# 4_CONN.net
KiCad netlist of a schematic drawn in Altium Designer
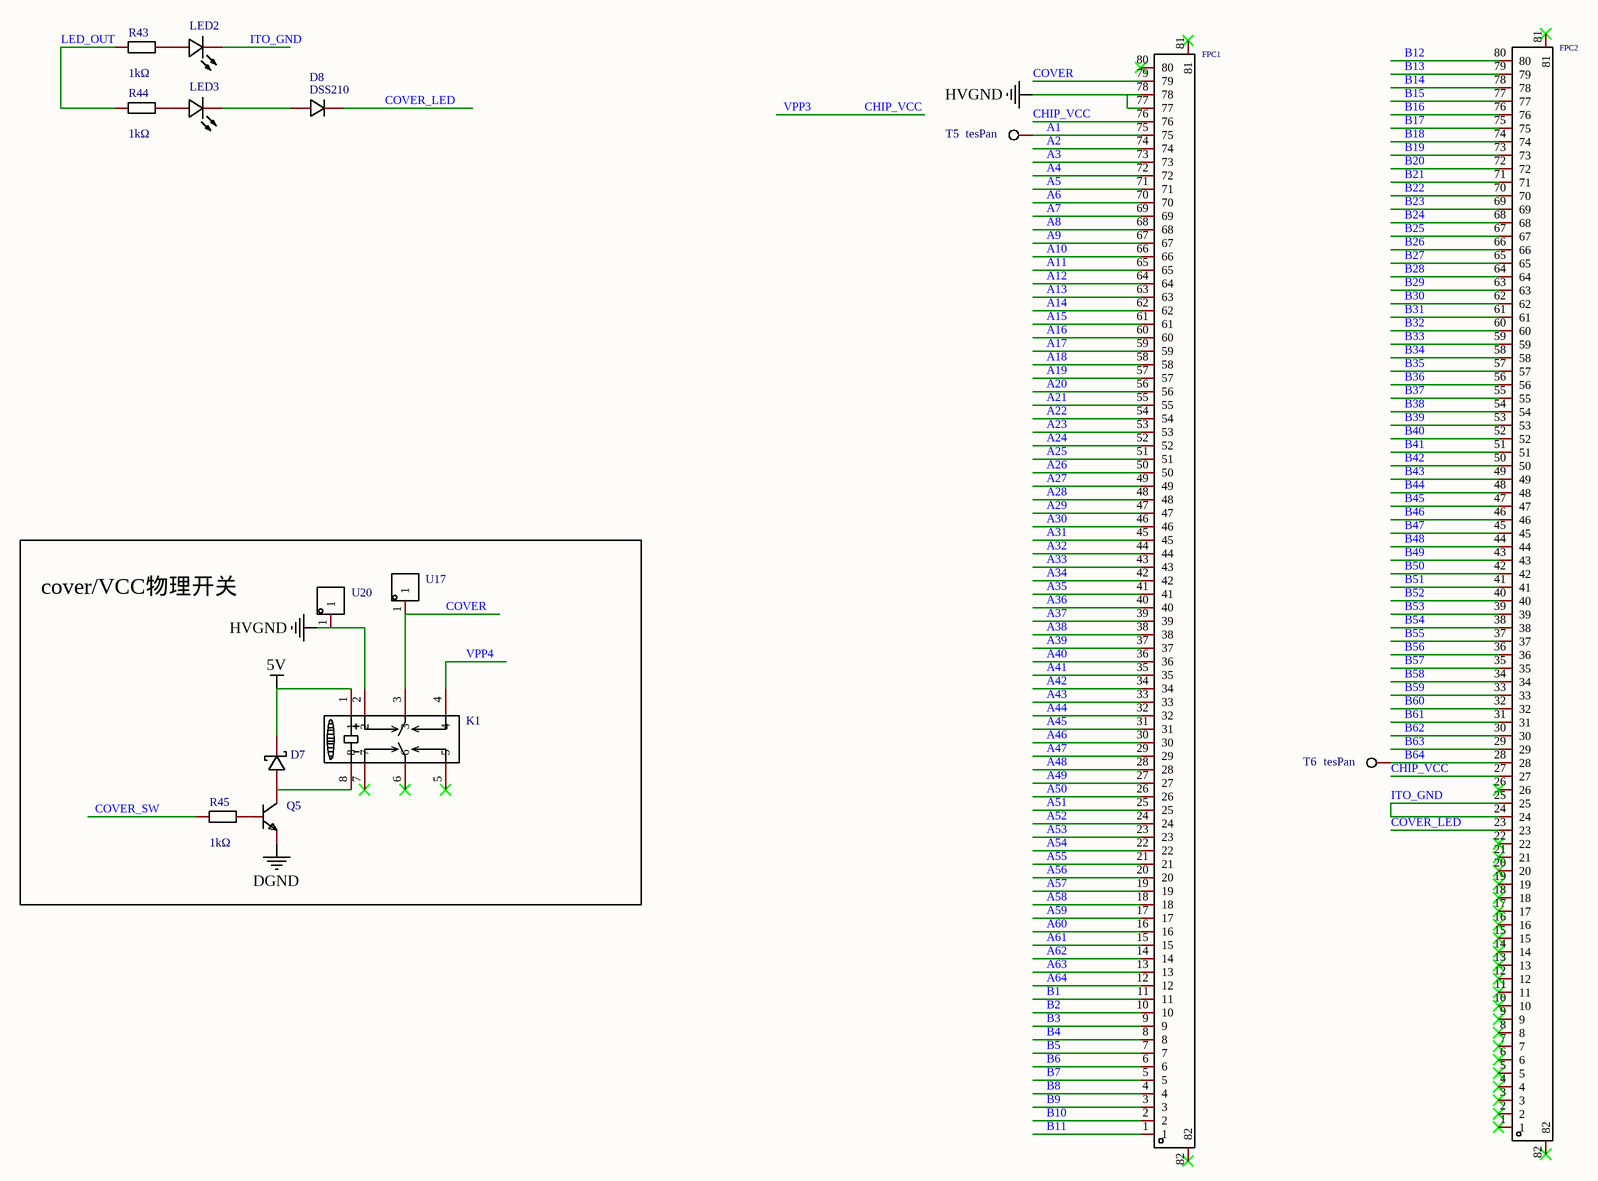
[diagram p0: 4_CONN.schdoc]

(export (version "E")
  (design (tool "Eeschema 10.0.6"))
  (components
    (comp (ref "D7")
      (value "B5819W SL")
      (description "直流反向耐压(Vr):40V;平均整流电流(Io):1A;正向压降(Vf):600mV@1A;")
      (fields (field (name "MANUFACTURER") "CJ(江苏长电/长晶)"))
      (libsource (lib "altium-import") (part "root_3_B5819W SL_"))
    )
    (comp (ref "D8")
      (value "DSS210")
      (fields (field (name "NAME") "DSS210") (field (name "MANUFACTURER") "Bourne Semicon (Shenzhen)"))
      (libsource (lib "altium-import") (part "root_0_DSS210_SOD-123_L2.8-W1.8-LS3.7-FD_"))
    )
    (comp (ref "FPC1")
      (value "FH28H-80S-0.5SH(05)")
      (description "间距:0.5mm;触点数量:80;锁定特性:翻盖式;安装类型:卧贴;触点类型:下接;")
      (fields (field (name "MANUFACTURER") "HRS(广濑)"))
      (libsource (lib "altium-import") (part "root_2_mirrored_FH28H-80S-0.5SH(05)_"))
    )
    (comp (ref "FPC2")
      (value "FH28H-80S-0.5SH(05)")
      (description "间距:0.5mm;触点数量:80;锁定特性:翻盖式;安装类型:卧贴;触点类型:下接;")
      (fields (field (name "MANUFACTURER") "HRS(广濑)"))
      (libsource (lib "altium-import") (part "root_2_mirrored_FH28H-80S-0.5SH(05)_"))
    )
    (comp (ref "K1")
      (value "G6K-2F-Y-TR DC5")
      (description "线圈电压:-;触点形式:-;最大切换电压:-;最大切换电流:-;线圈类型:-;触点材料:-;")
      (fields (field (name "MANUFACTURER") "OMRON(欧姆龙)"))
      (libsource (lib "altium-import") (part "root_2_mirrored_G6K-2F-Y-TR DC5_"))
    )
    (comp (ref "LED2")
      (value "LED0402-YELLOW")
      (libsource (lib "altium-import") (part "root_2_LED0402-YELLOW_"))
    )
    (comp (ref "LED3")
      (value "LED0402-YELLOW")
      (libsource (lib "altium-import") (part "root_2_LED0402-YELLOW_"))
    )
    (comp (ref "Q5")
      (value "S8050 J3Y_C2146")
      (fields (field (name "MANUFACTURER") "CJ(江苏长电/长晶)") (field (name "MANUFACTURER PART") "S8050 J3Y"))
      (libsource (lib "altium-import") (part "root_0_S8050 J3Y_C2146_"))
    )
    (comp (ref "R43")
      (value "1kΩ")
      (description "电阻类型:厚膜电阻;阻值:1kΩ;精度:±1%;功率:62.5mW;")
      (fields
        (field (name "MANUFACTURER") "UNI-ROYAL(厚声)")
        (field (name "MANUFACTURER PART") "0402WGF1001TCE")
      )
      (libsource (lib "altium-import") (part "root_0_0402WGF1001TCE_"))
    )
    (comp (ref "R44")
      (value "1kΩ")
      (description "电阻类型:厚膜电阻;阻值:1kΩ;精度:±1%;功率:62.5mW;")
      (fields
        (field (name "MANUFACTURER") "UNI-ROYAL(厚声)")
        (field (name "MANUFACTURER PART") "0402WGF1001TCE")
      )
      (libsource (lib "altium-import") (part "root_0_0402WGF1001TCE_"))
    )
    (comp (ref "R45")
      (value "1kΩ")
      (description "电阻类型:厚膜电阻;阻值:1kΩ;精度:±1%;功率:62.5mW;")
      (fields
        (field (name "MANUFACTURER") "UNI-ROYAL(厚声)")
        (field (name "MANUFACTURER PART") "0402WGF1001TCE")
      )
      (libsource (lib "altium-import") (part "root_0_0402WGF1001TCE_"))
    )
    (comp (ref "T5")
      (value "tesPan")
      (fields (field (name "NAME") "tesPan"))
      (libsource (lib "altium-import") (part "root_1_tesPan_"))
    )
    (comp (ref "T6")
      (value "tesPan")
      (fields (field (name "NAME") "tesPan"))
      (libsource (lib "altium-import") (part "root_1_tesPan_"))
    )
    (comp (ref "U17")
      (value "5003")
      (description "类型:测试环;全长/全高:7.62mm;工作高度:-;接触电阻:-;弹性寿命:-;额定电流:-;额定电压:-;触头材质:磷青铜;触头镀层:-;工作温度范围:-;")
      (fields (field (name "MANUFACTURER") "Keystone"))
      (libsource (lib "altium-import") (part "root_1_5003_"))
    )
    (comp (ref "U20")
      (value "5003")
      (description "类型:测试环;全长/全高:7.62mm;工作高度:-;接触电阻:-;弹性寿命:-;额定电流:-;额定电压:-;触头材质:磷青铜;触头镀层:-;工作温度范围:-;")
      (fields (field (name "MANUFACTURER") "Keystone"))
      (libsource (lib "altium-import") (part "root_1_5003_"))
    )
  )
  (nets
    (net (code "1") (name "/A1") (class "Default")
      (node (ref "FPC1") (pin "75") (pinfunction "75_75") (pintype "passive"))
      (node (ref "T5") (pin "1") (pinfunction "1_1") (pintype "passive"))
    )
    (net (code "2") (name "/A2") (class "Default")
      (node (ref "FPC1") (pin "74") (pinfunction "74_74") (pintype "passive"))
    )
    (net (code "3") (name "/A3") (class "Default")
      (node (ref "FPC1") (pin "73") (pinfunction "73_73") (pintype "passive"))
    )
    (net (code "4") (name "/A4") (class "Default")
      (node (ref "FPC1") (pin "72") (pinfunction "72_72") (pintype "passive"))
    )
    (net (code "5") (name "/A5") (class "Default")
      (node (ref "FPC1") (pin "71") (pinfunction "71_71") (pintype "passive"))
    )
    (net (code "6") (name "/A6") (class "Default")
      (node (ref "FPC1") (pin "70") (pinfunction "70_70") (pintype "passive"))
    )
    (net (code "7") (name "/A7") (class "Default")
      (node (ref "FPC1") (pin "69") (pinfunction "69_69") (pintype "passive"))
    )
    (net (code "8") (name "/A8") (class "Default")
      (node (ref "FPC1") (pin "68") (pinfunction "68_68") (pintype "passive"))
    )
    (net (code "9") (name "/A9") (class "Default")
      (node (ref "FPC1") (pin "67") (pinfunction "67_67") (pintype "passive"))
    )
    (net (code "10") (name "/A10") (class "Default")
      (node (ref "FPC1") (pin "66") (pinfunction "66_66") (pintype "passive"))
    )
    (net (code "11") (name "/A11") (class "Default")
      (node (ref "FPC1") (pin "65") (pinfunction "65_65") (pintype "passive"))
    )
    (net (code "12") (name "/A12") (class "Default")
      (node (ref "FPC1") (pin "64") (pinfunction "64_64") (pintype "passive"))
    )
    (net (code "13") (name "/A13") (class "Default")
      (node (ref "FPC1") (pin "63") (pinfunction "63_63") (pintype "passive"))
    )
    (net (code "14") (name "/A14") (class "Default")
      (node (ref "FPC1") (pin "62") (pinfunction "62_62") (pintype "passive"))
    )
    (net (code "15") (name "/A15") (class "Default")
      (node (ref "FPC1") (pin "61") (pinfunction "61_61") (pintype "passive"))
    )
    (net (code "16") (name "/A16") (class "Default")
      (node (ref "FPC1") (pin "60") (pinfunction "60_60") (pintype "passive"))
    )
    (net (code "17") (name "/A17") (class "Default")
      (node (ref "FPC1") (pin "59") (pinfunction "59_59") (pintype "passive"))
    )
    (net (code "18") (name "/A18") (class "Default")
      (node (ref "FPC1") (pin "58") (pinfunction "58_58") (pintype "passive"))
    )
    (net (code "19") (name "/A19") (class "Default")
      (node (ref "FPC1") (pin "57") (pinfunction "57_57") (pintype "passive"))
    )
    (net (code "20") (name "/A20") (class "Default")
      (node (ref "FPC1") (pin "56") (pinfunction "56_56") (pintype "passive"))
    )
    (net (code "21") (name "/A21") (class "Default")
      (node (ref "FPC1") (pin "55") (pinfunction "55_55") (pintype "passive"))
    )
    (net (code "22") (name "/A22") (class "Default")
      (node (ref "FPC1") (pin "54") (pinfunction "54_54") (pintype "passive"))
    )
    (net (code "23") (name "/A23") (class "Default")
      (node (ref "FPC1") (pin "53") (pinfunction "53_53") (pintype "passive"))
    )
    (net (code "24") (name "/A24") (class "Default")
      (node (ref "FPC1") (pin "52") (pinfunction "52_52") (pintype "passive"))
    )
    (net (code "25") (name "/A25") (class "Default")
      (node (ref "FPC1") (pin "51") (pinfunction "51_51") (pintype "passive"))
    )
    (net (code "26") (name "/A26") (class "Default")
      (node (ref "FPC1") (pin "50") (pinfunction "50_50") (pintype "passive"))
    )
    (net (code "27") (name "/A27") (class "Default")
      (node (ref "FPC1") (pin "49") (pinfunction "49_49") (pintype "passive"))
    )
    (net (code "28") (name "/A28") (class "Default")
      (node (ref "FPC1") (pin "48") (pinfunction "48_48") (pintype "passive"))
    )
    (net (code "29") (name "/A29") (class "Default")
      (node (ref "FPC1") (pin "47") (pinfunction "47_47") (pintype "passive"))
    )
    (net (code "30") (name "/A30") (class "Default")
      (node (ref "FPC1") (pin "46") (pinfunction "46_46") (pintype "passive"))
    )
    (net (code "31") (name "/A31") (class "Default")
      (node (ref "FPC1") (pin "45") (pinfunction "45_45") (pintype "passive"))
    )
    (net (code "32") (name "/A32") (class "Default")
      (node (ref "FPC1") (pin "44") (pinfunction "44_44") (pintype "passive"))
    )
    (net (code "33") (name "/A33") (class "Default")
      (node (ref "FPC1") (pin "43") (pinfunction "43_43") (pintype "passive"))
    )
    (net (code "34") (name "/A34") (class "Default")
      (node (ref "FPC1") (pin "42") (pinfunction "42_42") (pintype "passive"))
    )
    (net (code "35") (name "/A35") (class "Default")
      (node (ref "FPC1") (pin "41") (pinfunction "41_41") (pintype "passive"))
    )
    (net (code "36") (name "/A36") (class "Default")
      (node (ref "FPC1") (pin "40") (pinfunction "40_40") (pintype "passive"))
    )
    (net (code "37") (name "/A37") (class "Default")
      (node (ref "FPC1") (pin "39") (pinfunction "39_39") (pintype "passive"))
    )
    (net (code "38") (name "/A38") (class "Default")
      (node (ref "FPC1") (pin "38") (pinfunction "38_38") (pintype "passive"))
    )
    (net (code "39") (name "/A39") (class "Default")
      (node (ref "FPC1") (pin "37") (pinfunction "37_37") (pintype "passive"))
    )
    (net (code "40") (name "/A40") (class "Default")
      (node (ref "FPC1") (pin "36") (pinfunction "36_36") (pintype "passive"))
    )
    (net (code "41") (name "/A41") (class "Default")
      (node (ref "FPC1") (pin "35") (pinfunction "35_35") (pintype "passive"))
    )
    (net (code "42") (name "/A42") (class "Default")
      (node (ref "FPC1") (pin "34") (pinfunction "34_34") (pintype "passive"))
    )
    (net (code "43") (name "/A43") (class "Default")
      (node (ref "FPC1") (pin "33") (pinfunction "33_33") (pintype "passive"))
    )
    (net (code "44") (name "/A44") (class "Default")
      (node (ref "FPC1") (pin "32") (pinfunction "32_32") (pintype "passive"))
    )
    (net (code "45") (name "/A45") (class "Default")
      (node (ref "FPC1") (pin "31") (pinfunction "31_31") (pintype "passive"))
    )
    (net (code "46") (name "/A46") (class "Default")
      (node (ref "FPC1") (pin "30") (pinfunction "30_30") (pintype "passive"))
    )
    (net (code "47") (name "/A47") (class "Default")
      (node (ref "FPC1") (pin "29") (pinfunction "29_29") (pintype "passive"))
    )
    (net (code "48") (name "/A48") (class "Default")
      (node (ref "FPC1") (pin "28") (pinfunction "28_28") (pintype "passive"))
    )
    (net (code "49") (name "/A49") (class "Default")
      (node (ref "FPC1") (pin "27") (pinfunction "27_27") (pintype "passive"))
    )
    (net (code "50") (name "/A50") (class "Default")
      (node (ref "FPC1") (pin "26") (pinfunction "26_26") (pintype "passive"))
    )
    (net (code "51") (name "/A51") (class "Default")
      (node (ref "FPC1") (pin "25") (pinfunction "25_25") (pintype "passive"))
    )
    (net (code "52") (name "/A52") (class "Default")
      (node (ref "FPC1") (pin "24") (pinfunction "24_24") (pintype "passive"))
    )
    (net (code "53") (name "/A53") (class "Default")
      (node (ref "FPC1") (pin "23") (pinfunction "23_23") (pintype "passive"))
    )
    (net (code "54") (name "/A54") (class "Default")
      (node (ref "FPC1") (pin "22") (pinfunction "22_22") (pintype "passive"))
    )
    (net (code "55") (name "/A55") (class "Default")
      (node (ref "FPC1") (pin "21") (pinfunction "21_21") (pintype "passive"))
    )
    (net (code "56") (name "/A56") (class "Default")
      (node (ref "FPC1") (pin "20") (pinfunction "20_20") (pintype "passive"))
    )
    (net (code "57") (name "/A57") (class "Default")
      (node (ref "FPC1") (pin "19") (pinfunction "19_19") (pintype "passive"))
    )
    (net (code "58") (name "/A58") (class "Default")
      (node (ref "FPC1") (pin "18") (pinfunction "18_18") (pintype "passive"))
    )
    (net (code "59") (name "/A59") (class "Default")
      (node (ref "FPC1") (pin "17") (pinfunction "17_17") (pintype "passive"))
    )
    (net (code "60") (name "/A60") (class "Default")
      (node (ref "FPC1") (pin "16") (pinfunction "16_16") (pintype "passive"))
    )
    (net (code "61") (name "/A61") (class "Default")
      (node (ref "FPC1") (pin "15") (pinfunction "15_15") (pintype "passive"))
    )
    (net (code "62") (name "/A62") (class "Default")
      (node (ref "FPC1") (pin "14") (pinfunction "14_14") (pintype "passive"))
    )
    (net (code "63") (name "/A63") (class "Default")
      (node (ref "FPC1") (pin "13") (pinfunction "13_13") (pintype "passive"))
    )
    (net (code "64") (name "/A64") (class "Default")
      (node (ref "FPC1") (pin "12") (pinfunction "12_12") (pintype "passive"))
    )
    (net (code "65") (name "/B1") (class "Default")
      (node (ref "FPC1") (pin "11") (pinfunction "11_11") (pintype "passive"))
    )
    (net (code "66") (name "/B2") (class "Default")
      (node (ref "FPC1") (pin "10") (pinfunction "10_10") (pintype "passive"))
    )
    (net (code "67") (name "/B3") (class "Default")
      (node (ref "FPC1") (pin "9") (pinfunction "9_9") (pintype "passive"))
    )
    (net (code "68") (name "/B4") (class "Default")
      (node (ref "FPC1") (pin "8") (pinfunction "8_8") (pintype "passive"))
    )
    (net (code "69") (name "/B5") (class "Default")
      (node (ref "FPC1") (pin "7") (pinfunction "7_7") (pintype "passive"))
    )
    (net (code "70") (name "/B6") (class "Default")
      (node (ref "FPC1") (pin "6") (pinfunction "6_6") (pintype "passive"))
    )
    (net (code "71") (name "/B7") (class "Default")
      (node (ref "FPC1") (pin "5") (pinfunction "5_5") (pintype "passive"))
    )
    (net (code "72") (name "/B8") (class "Default")
      (node (ref "FPC1") (pin "4") (pinfunction "4_4") (pintype "passive"))
    )
    (net (code "73") (name "/B9") (class "Default")
      (node (ref "FPC1") (pin "3") (pinfunction "3_3") (pintype "passive"))
    )
    (net (code "74") (name "/B10") (class "Default")
      (node (ref "FPC1") (pin "2") (pinfunction "2_2") (pintype "passive"))
    )
    (net (code "75") (name "/B11") (class "Default")
      (node (ref "FPC1") (pin "1") (pinfunction "1_1") (pintype "passive"))
    )
    (net (code "76") (name "/B12") (class "Default")
      (node (ref "FPC2") (pin "80") (pinfunction "80_80") (pintype "passive"))
    )
    (net (code "77") (name "/B13") (class "Default")
      (node (ref "FPC2") (pin "79") (pinfunction "79_79") (pintype "passive"))
    )
    (net (code "78") (name "/B14") (class "Default")
      (node (ref "FPC2") (pin "78") (pinfunction "78_78") (pintype "passive"))
    )
    (net (code "79") (name "/B15") (class "Default")
      (node (ref "FPC2") (pin "77") (pinfunction "77_77") (pintype "passive"))
    )
    (net (code "80") (name "/B16") (class "Default")
      (node (ref "FPC2") (pin "76") (pinfunction "76_76") (pintype "passive"))
    )
    (net (code "81") (name "/B17") (class "Default")
      (node (ref "FPC2") (pin "75") (pinfunction "75_75") (pintype "passive"))
    )
    (net (code "82") (name "/B18") (class "Default")
      (node (ref "FPC2") (pin "74") (pinfunction "74_74") (pintype "passive"))
    )
    (net (code "83") (name "/B19") (class "Default")
      (node (ref "FPC2") (pin "73") (pinfunction "73_73") (pintype "passive"))
    )
    (net (code "84") (name "/B20") (class "Default")
      (node (ref "FPC2") (pin "72") (pinfunction "72_72") (pintype "passive"))
    )
    (net (code "85") (name "/B21") (class "Default")
      (node (ref "FPC2") (pin "71") (pinfunction "71_71") (pintype "passive"))
    )
    (net (code "86") (name "/B22") (class "Default")
      (node (ref "FPC2") (pin "70") (pinfunction "70_70") (pintype "passive"))
    )
    (net (code "87") (name "/B23") (class "Default")
      (node (ref "FPC2") (pin "69") (pinfunction "69_69") (pintype "passive"))
    )
    (net (code "88") (name "/B24") (class "Default")
      (node (ref "FPC2") (pin "68") (pinfunction "68_68") (pintype "passive"))
    )
    (net (code "89") (name "/B25") (class "Default")
      (node (ref "FPC2") (pin "67") (pinfunction "67_67") (pintype "passive"))
    )
    (net (code "90") (name "/B26") (class "Default")
      (node (ref "FPC2") (pin "66") (pinfunction "66_66") (pintype "passive"))
    )
    (net (code "91") (name "/B27") (class "Default")
      (node (ref "FPC2") (pin "65") (pinfunction "65_65") (pintype "passive"))
    )
    (net (code "92") (name "/B28") (class "Default")
      (node (ref "FPC2") (pin "64") (pinfunction "64_64") (pintype "passive"))
    )
    (net (code "93") (name "/B29") (class "Default")
      (node (ref "FPC2") (pin "63") (pinfunction "63_63") (pintype "passive"))
    )
    (net (code "94") (name "/B30") (class "Default")
      (node (ref "FPC2") (pin "62") (pinfunction "62_62") (pintype "passive"))
    )
    (net (code "95") (name "/B31") (class "Default")
      (node (ref "FPC2") (pin "61") (pinfunction "61_61") (pintype "passive"))
    )
    (net (code "96") (name "/B32") (class "Default")
      (node (ref "FPC2") (pin "60") (pinfunction "60_60") (pintype "passive"))
    )
    (net (code "97") (name "/B33") (class "Default")
      (node (ref "FPC2") (pin "59") (pinfunction "59_59") (pintype "passive"))
    )
    (net (code "98") (name "/B34") (class "Default")
      (node (ref "FPC2") (pin "58") (pinfunction "58_58") (pintype "passive"))
    )
    (net (code "99") (name "/B35") (class "Default")
      (node (ref "FPC2") (pin "57") (pinfunction "57_57") (pintype "passive"))
    )
    (net (code "100") (name "/B36") (class "Default")
      (node (ref "FPC2") (pin "56") (pinfunction "56_56") (pintype "passive"))
    )
    (net (code "101") (name "/B37") (class "Default")
      (node (ref "FPC2") (pin "55") (pinfunction "55_55") (pintype "passive"))
    )
    (net (code "102") (name "/B38") (class "Default")
      (node (ref "FPC2") (pin "54") (pinfunction "54_54") (pintype "passive"))
    )
    (net (code "103") (name "/B39") (class "Default")
      (node (ref "FPC2") (pin "53") (pinfunction "53_53") (pintype "passive"))
    )
    (net (code "104") (name "/B40") (class "Default")
      (node (ref "FPC2") (pin "52") (pinfunction "52_52") (pintype "passive"))
    )
    (net (code "105") (name "/B41") (class "Default")
      (node (ref "FPC2") (pin "51") (pinfunction "51_51") (pintype "passive"))
    )
    (net (code "106") (name "/B42") (class "Default")
      (node (ref "FPC2") (pin "50") (pinfunction "50_50") (pintype "passive"))
    )
    (net (code "107") (name "/B43") (class "Default")
      (node (ref "FPC2") (pin "49") (pinfunction "49_49") (pintype "passive"))
    )
    (net (code "108") (name "/B44") (class "Default")
      (node (ref "FPC2") (pin "48") (pinfunction "48_48") (pintype "passive"))
    )
    (net (code "109") (name "/B45") (class "Default")
      (node (ref "FPC2") (pin "47") (pinfunction "47_47") (pintype "passive"))
    )
    (net (code "110") (name "/B46") (class "Default")
      (node (ref "FPC2") (pin "46") (pinfunction "46_46") (pintype "passive"))
    )
    (net (code "111") (name "/B47") (class "Default")
      (node (ref "FPC2") (pin "45") (pinfunction "45_45") (pintype "passive"))
    )
    (net (code "112") (name "/B48") (class "Default")
      (node (ref "FPC2") (pin "44") (pinfunction "44_44") (pintype "passive"))
    )
    (net (code "113") (name "/B49") (class "Default")
      (node (ref "FPC2") (pin "43") (pinfunction "43_43") (pintype "passive"))
    )
    (net (code "114") (name "/B50") (class "Default")
      (node (ref "FPC2") (pin "42") (pinfunction "42_42") (pintype "passive"))
    )
    (net (code "115") (name "/B51") (class "Default")
      (node (ref "FPC2") (pin "41") (pinfunction "41_41") (pintype "passive"))
    )
    (net (code "116") (name "/B52") (class "Default")
      (node (ref "FPC2") (pin "40") (pinfunction "40_40") (pintype "passive"))
    )
    (net (code "117") (name "/B53") (class "Default")
      (node (ref "FPC2") (pin "39") (pinfunction "39_39") (pintype "passive"))
    )
    (net (code "118") (name "/B54") (class "Default")
      (node (ref "FPC2") (pin "38") (pinfunction "38_38") (pintype "passive"))
    )
    (net (code "119") (name "/B55") (class "Default")
      (node (ref "FPC2") (pin "37") (pinfunction "37_37") (pintype "passive"))
    )
    (net (code "120") (name "/B56") (class "Default")
      (node (ref "FPC2") (pin "36") (pinfunction "36_36") (pintype "passive"))
    )
    (net (code "121") (name "/B57") (class "Default")
      (node (ref "FPC2") (pin "35") (pinfunction "35_35") (pintype "passive"))
    )
    (net (code "122") (name "/B58") (class "Default")
      (node (ref "FPC2") (pin "34") (pinfunction "34_34") (pintype "passive"))
    )
    (net (code "123") (name "/B59") (class "Default")
      (node (ref "FPC2") (pin "33") (pinfunction "33_33") (pintype "passive"))
    )
    (net (code "124") (name "/B60") (class "Default")
      (node (ref "FPC2") (pin "32") (pinfunction "32_32") (pintype "passive"))
    )
    (net (code "125") (name "/B61") (class "Default")
      (node (ref "FPC2") (pin "31") (pinfunction "31_31") (pintype "passive"))
    )
    (net (code "126") (name "/B62") (class "Default")
      (node (ref "FPC2") (pin "30") (pinfunction "30_30") (pintype "passive"))
    )
    (net (code "127") (name "/B63") (class "Default")
      (node (ref "FPC2") (pin "29") (pinfunction "29_29") (pintype "passive"))
    )
    (net (code "128") (name "/B64") (class "Default")
      (node (ref "FPC2") (pin "28") (pinfunction "28_28") (pintype "passive"))
      (node (ref "T6") (pin "1") (pinfunction "1_1") (pintype "passive"))
    )
    (net (code "129") (name "/CHIP_VCC") (class "Default")
      (node (ref "FPC1") (pin "76") (pinfunction "76_76") (pintype "passive"))
      (node (ref "FPC2") (pin "27") (pinfunction "27_27") (pintype "passive"))
    )
    (net (code "130") (name "/COVER") (class "Default")
      (node (ref "FPC1") (pin "79") (pinfunction "79_79") (pintype "passive"))
      (node (ref "K1") (pin "3") (pinfunction "3_3") (pintype "passive"))
      (node (ref "U17") (pin "1") (pinfunction "1_1") (pintype "passive"))
    )
    (net (code "131") (name "/COVER_LED") (class "Default")
      (node (ref "D8") (pin "2") (pinfunction "K_2") (pintype "passive"))
      (node (ref "FPC2") (pin "23") (pinfunction "23_23") (pintype "passive"))
    )
    (net (code "132") (name "/COVER_SW") (class "Default")
      (node (ref "R45") (pin "1") (pinfunction "1_1") (pintype "passive"))
    )
    (net (code "133") (name "/ITO_GND") (class "Default")
      (node (ref "FPC2") (pin "24") (pinfunction "24_24") (pintype "passive"))
      (node (ref "FPC2") (pin "25") (pinfunction "25_25") (pintype "passive"))
      (node (ref "LED2") (pin "1") (pinfunction "-_1") (pintype "passive"))
    )
    (net (code "134") (name "/LED_OUT") (class "Default")
      (node (ref "R43") (pin "1") (pinfunction "1_1") (pintype "passive"))
      (node (ref "R44") (pin "1") (pinfunction "1_1") (pintype "passive"))
    )
    (net (code "135") (name "/VPP4") (class "Default")
      (node (ref "K1") (pin "4") (pinfunction "4_4") (pintype "passive"))
    )
    (net (code "136") (name "5V") (class "Default")
      (node (ref "D7") (pin "1") (pinfunction "-_1") (pintype "passive"))
      (node (ref "K1") (pin "1") (pinfunction "1_1") (pintype "passive"))
    )
    (net (code "137") (name "DGND") (class "Default")
      (node (ref "Q5") (pin "2") (pinfunction "E_2") (pintype "passive"))
    )
    (net (code "138") (name "HVGND") (class "Default")
      (node (ref "FPC1") (pin "77") (pinfunction "77_77") (pintype "passive"))
      (node (ref "FPC1") (pin "78") (pinfunction "78_78") (pintype "passive"))
      (node (ref "K1") (pin "2") (pinfunction "2_2") (pintype "passive"))
      (node (ref "U20") (pin "1") (pinfunction "1_1") (pintype "passive"))
    )
    (net (code "139") (name "Net-(D7-+)") (class "Default")
      (node (ref "D7") (pin "2") (pinfunction "+_2") (pintype "passive"))
      (node (ref "K1") (pin "8") (pinfunction "8_8") (pintype "passive"))
      (node (ref "Q5") (pin "3") (pinfunction "C_3") (pintype "passive"))
    )
    (net (code "140") (name "Net-(D8-A)") (class "Default")
      (node (ref "D8") (pin "1") (pinfunction "A_1") (pintype "passive"))
      (node (ref "LED3") (pin "1") (pinfunction "-_1") (pintype "passive"))
    )
    (net (code "141") (name "Net-(LED2-+)") (class "Default")
      (node (ref "LED2") (pin "2") (pinfunction "+_2") (pintype "passive"))
      (node (ref "R43") (pin "2") (pinfunction "2_2") (pintype "passive"))
    )
    (net (code "142") (name "Net-(LED3-+)") (class "Default")
      (node (ref "LED3") (pin "2") (pinfunction "+_2") (pintype "passive"))
      (node (ref "R44") (pin "2") (pinfunction "2_2") (pintype "passive"))
    )
    (net (code "143") (name "Net-(Q5-B)") (class "Default")
      (node (ref "Q5") (pin "1") (pinfunction "B_1") (pintype "passive"))
      (node (ref "R45") (pin "2") (pinfunction "2_2") (pintype "passive"))
    )
    (net (code "144") (name "unconnected-(FPC1-Pad80)") (class "Default")
      (node (ref "FPC1") (pin "80") (pinfunction "80_80") (pintype "passive+no_connect"))
    )
    (net (code "145") (name "unconnected-(FPC1-Pad81)") (class "Default")
      (node (ref "FPC1") (pin "81") (pinfunction "81_81") (pintype "passive+no_connect"))
    )
    (net (code "146") (name "unconnected-(FPC1-Pad82)") (class "Default")
      (node (ref "FPC1") (pin "82") (pinfunction "82_82") (pintype "passive+no_connect"))
    )
    (net (code "147") (name "unconnected-(FPC2-Pad1)") (class "Default")
      (node (ref "FPC2") (pin "1") (pinfunction "1_1") (pintype "passive+no_connect"))
    )
    (net (code "148") (name "unconnected-(FPC2-Pad2)") (class "Default")
      (node (ref "FPC2") (pin "2") (pinfunction "2_2") (pintype "passive+no_connect"))
    )
    (net (code "149") (name "unconnected-(FPC2-Pad3)") (class "Default")
      (node (ref "FPC2") (pin "3") (pinfunction "3_3") (pintype "passive+no_connect"))
    )
    (net (code "150") (name "unconnected-(FPC2-Pad4)") (class "Default")
      (node (ref "FPC2") (pin "4") (pinfunction "4_4") (pintype "passive+no_connect"))
    )
    (net (code "151") (name "unconnected-(FPC2-Pad5)") (class "Default")
      (node (ref "FPC2") (pin "5") (pinfunction "5_5") (pintype "passive+no_connect"))
    )
    (net (code "152") (name "unconnected-(FPC2-Pad6)") (class "Default")
      (node (ref "FPC2") (pin "6") (pinfunction "6_6") (pintype "passive+no_connect"))
    )
    (net (code "153") (name "unconnected-(FPC2-Pad7)") (class "Default")
      (node (ref "FPC2") (pin "7") (pinfunction "7_7") (pintype "passive+no_connect"))
    )
    (net (code "154") (name "unconnected-(FPC2-Pad8)") (class "Default")
      (node (ref "FPC2") (pin "8") (pinfunction "8_8") (pintype "passive+no_connect"))
    )
    (net (code "155") (name "unconnected-(FPC2-Pad9)") (class "Default")
      (node (ref "FPC2") (pin "9") (pinfunction "9_9") (pintype "passive+no_connect"))
    )
    (net (code "156") (name "unconnected-(FPC2-Pad10)") (class "Default")
      (node (ref "FPC2") (pin "10") (pinfunction "10_10") (pintype "passive+no_connect"))
    )
    (net (code "157") (name "unconnected-(FPC2-Pad11)") (class "Default")
      (node (ref "FPC2") (pin "11") (pinfunction "11_11") (pintype "passive+no_connect"))
    )
    (net (code "158") (name "unconnected-(FPC2-Pad12)") (class "Default")
      (node (ref "FPC2") (pin "12") (pinfunction "12_12") (pintype "passive+no_connect"))
    )
    (net (code "159") (name "unconnected-(FPC2-Pad13)") (class "Default")
      (node (ref "FPC2") (pin "13") (pinfunction "13_13") (pintype "passive+no_connect"))
    )
    (net (code "160") (name "unconnected-(FPC2-Pad14)") (class "Default")
      (node (ref "FPC2") (pin "14") (pinfunction "14_14") (pintype "passive+no_connect"))
    )
    (net (code "161") (name "unconnected-(FPC2-Pad15)") (class "Default")
      (node (ref "FPC2") (pin "15") (pinfunction "15_15") (pintype "passive+no_connect"))
    )
    (net (code "162") (name "unconnected-(FPC2-Pad16)") (class "Default")
      (node (ref "FPC2") (pin "16") (pinfunction "16_16") (pintype "passive+no_connect"))
    )
    (net (code "163") (name "unconnected-(FPC2-Pad17)") (class "Default")
      (node (ref "FPC2") (pin "17") (pinfunction "17_17") (pintype "passive+no_connect"))
    )
    (net (code "164") (name "unconnected-(FPC2-Pad18)") (class "Default")
      (node (ref "FPC2") (pin "18") (pinfunction "18_18") (pintype "passive+no_connect"))
    )
    (net (code "165") (name "unconnected-(FPC2-Pad19)") (class "Default")
      (node (ref "FPC2") (pin "19") (pinfunction "19_19") (pintype "passive+no_connect"))
    )
    (net (code "166") (name "unconnected-(FPC2-Pad20)") (class "Default")
      (node (ref "FPC2") (pin "20") (pinfunction "20_20") (pintype "passive+no_connect"))
    )
    (net (code "167") (name "unconnected-(FPC2-Pad21)") (class "Default")
      (node (ref "FPC2") (pin "21") (pinfunction "21_21") (pintype "passive+no_connect"))
    )
    (net (code "168") (name "unconnected-(FPC2-Pad22)") (class "Default")
      (node (ref "FPC2") (pin "22") (pinfunction "22_22") (pintype "passive+no_connect"))
    )
    (net (code "169") (name "unconnected-(FPC2-Pad26)") (class "Default")
      (node (ref "FPC2") (pin "26") (pinfunction "26_26") (pintype "passive+no_connect"))
    )
    (net (code "170") (name "unconnected-(FPC2-Pad81)") (class "Default")
      (node (ref "FPC2") (pin "81") (pinfunction "81_81") (pintype "passive+no_connect"))
    )
    (net (code "171") (name "unconnected-(FPC2-Pad82)") (class "Default")
      (node (ref "FPC2") (pin "82") (pinfunction "82_82") (pintype "passive+no_connect"))
    )
    (net (code "172") (name "unconnected-(K1-Pad5)") (class "Default")
      (node (ref "K1") (pin "5") (pinfunction "5_5") (pintype "passive+no_connect"))
    )
    (net (code "173") (name "unconnected-(K1-Pad6)") (class "Default")
      (node (ref "K1") (pin "6") (pinfunction "6_6") (pintype "passive+no_connect"))
    )
    (net (code "174") (name "unconnected-(K1-Pad7)") (class "Default")
      (node (ref "K1") (pin "7") (pinfunction "7_7") (pintype "passive+no_connect"))
    )
  )
)
